# LEDs.net
KiCad netlist of a schematic drawn in Altium Designer
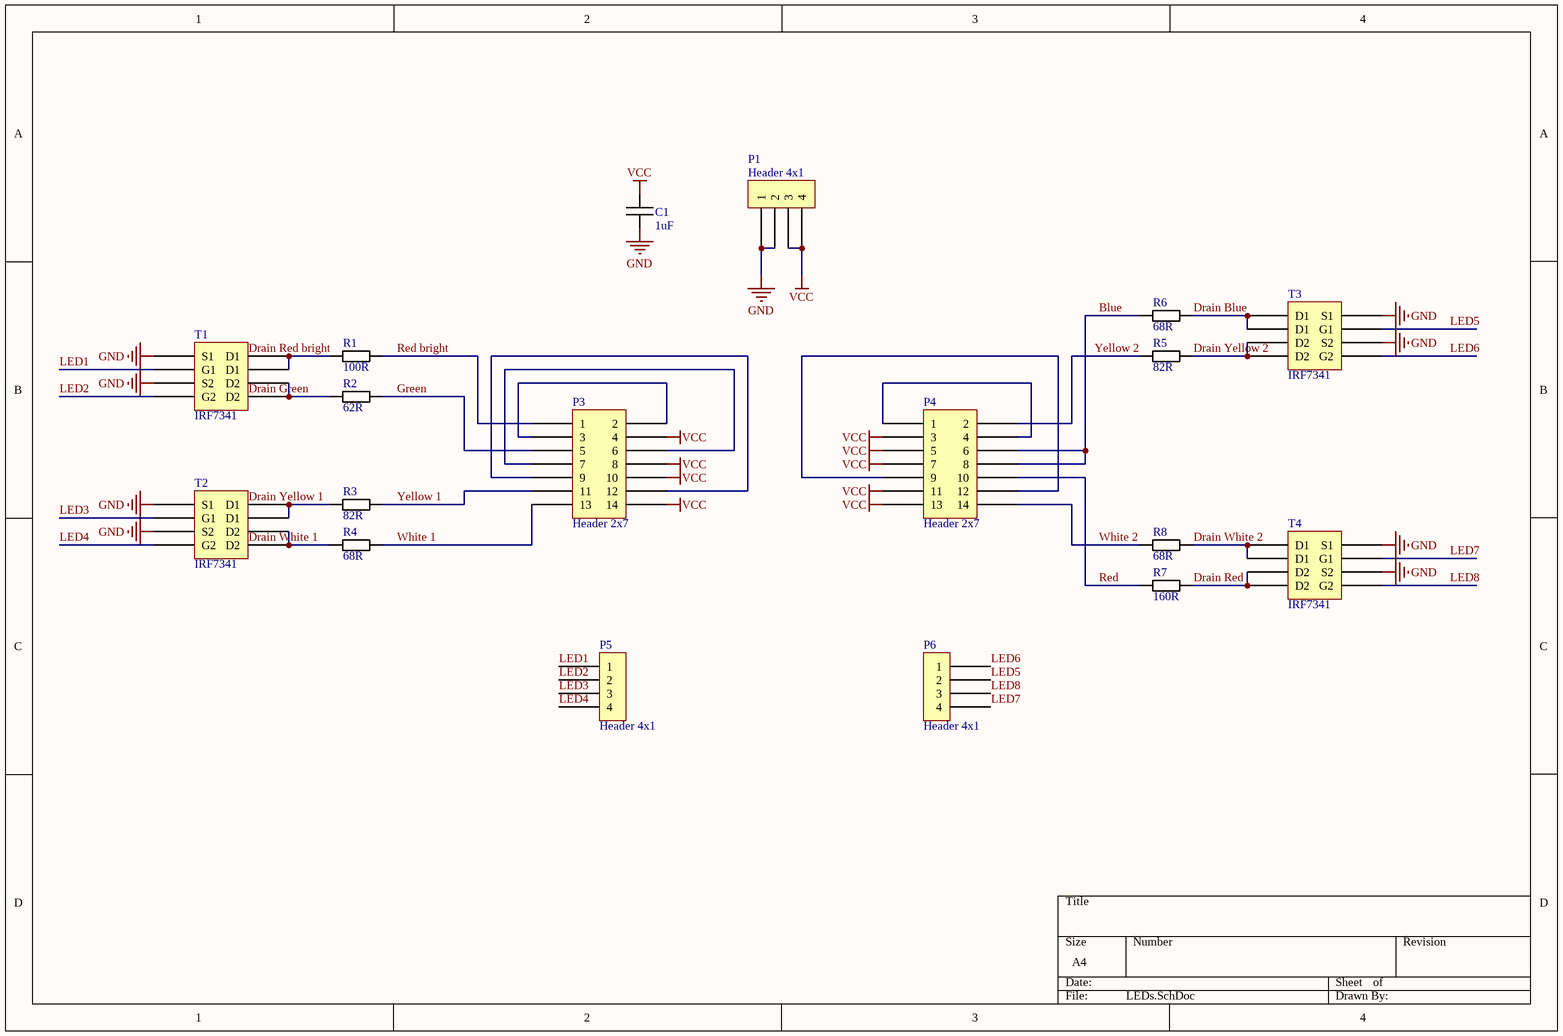
[diagram p0: LEDs.SchDoc]

(export (version "E")
  (design (tool "Eeschema 10.0.6"))
  (components
    (comp (ref "C1") (value "1uF") (footprint "C 0805 / 2012") (libsource (lib "LEDs") (part "Capacitor")))
    (comp (ref "P1")
      (value "Header 4x1")
      (footprint "Header 4x1 2.54mm")
      (libsource (lib "") (part "Header 4x1_1"))
    )
    (comp (ref "P3")
      (value "Header 2x7")
      (footprint "Header 7x2 2.54mm")
      (libsource (lib "LEDs") (part "Header 2x7"))
    )
    (comp (ref "P4")
      (value "Header 2x7")
      (footprint "Header 7x2 2.54mm")
      (libsource (lib "LEDs") (part "Header 2x7"))
    )
    (comp (ref "P5")
      (value "Header 4x1")
      (footprint "Header 4x1 2.54mm")
      (libsource (lib "") (part "Header 4x1_2"))
    )
    (comp (ref "P6")
      (value "Header 4x1")
      (footprint "Header 4x1 2.54mm")
      (libsource (lib "LEDs") (part "Header 4x1"))
    )
    (comp (ref "R1")
      (value "100R")
      (footprint "R 0805 / 2012")
      (description "Resistor")
      (libsource (lib "LEDs") (part "Resistor"))
    )
    (comp (ref "R2")
      (value "62R")
      (footprint "R 0805 / 2012")
      (description "Resistor")
      (libsource (lib "LEDs") (part "Resistor"))
    )
    (comp (ref "R3")
      (value "82R")
      (footprint "R 0805 / 2012")
      (description "Resistor")
      (libsource (lib "LEDs") (part "Resistor"))
    )
    (comp (ref "R4")
      (value "68R")
      (footprint "R 0805 / 2012")
      (description "Resistor")
      (libsource (lib "LEDs") (part "Resistor"))
    )
    (comp (ref "R5")
      (value "82R")
      (footprint "R 0805 / 2012")
      (description "Resistor")
      (libsource (lib "LEDs") (part "Resistor"))
    )
    (comp (ref "R6")
      (value "68R")
      (footprint "R 0805 / 2012")
      (description "Resistor")
      (libsource (lib "LEDs") (part "Resistor"))
    )
    (comp (ref "R7")
      (value "160R")
      (footprint "R 0805 / 2012")
      (description "Resistor")
      (libsource (lib "LEDs") (part "Resistor"))
    )
    (comp (ref "R8")
      (value "68R")
      (footprint "R 0805 / 2012")
      (description "Resistor")
      (libsource (lib "LEDs") (part "Resistor"))
    )
    (comp (ref "T1") (value "IRF7341") (footprint "SOIC8") (libsource (lib "") (part "IRF7341_1")))
    (comp (ref "T2") (value "IRF7341") (footprint "SOIC8") (libsource (lib "") (part "IRF7341_1")))
    (comp (ref "T3") (value "IRF7341") (footprint "SOIC8") (libsource (lib "LEDs") (part "IRF7341")))
    (comp (ref "T4") (value "IRF7341") (footprint "SOIC8") (libsource (lib "LEDs") (part "IRF7341")))
  )
  (nets
    (net (code "1") (name "/Blue") (class "Default")
      (node (ref "P4") (pin "6") (pinfunction "6_6") (pintype "passive"))
      (node (ref "P4") (pin "8") (pinfunction "8_8") (pintype "passive"))
      (node (ref "R6") (pin "1") (pinfunction "1_1") (pintype "passive"))
    )
    (net (code "2") (name "/Drain Blue") (class "Default")
      (node (ref "R6") (pin "2") (pinfunction "2_2") (pintype "passive"))
      (node (ref "T3") (pin "7") (pinfunction "D1_7") (pintype "passive"))
      (node (ref "T3") (pin "8") (pinfunction "D1_8") (pintype "passive"))
    )
    (net (code "4") (name "/Drain Red") (class "Default")
      (node (ref "R7") (pin "2") (pinfunction "2_2") (pintype "passive"))
      (node (ref "T4") (pin "5") (pinfunction "D2_5") (pintype "passive"))
      (node (ref "T4") (pin "6") (pinfunction "D2_6") (pintype "passive"))
    )
    (net (code "7") (name "/Drain White 2") (class "Default")
      (node (ref "R8") (pin "2") (pinfunction "2_2") (pintype "passive"))
      (node (ref "T4") (pin "7") (pinfunction "D1_7") (pintype "passive"))
      (node (ref "T4") (pin "8") (pinfunction "D1_8") (pintype "passive"))
    )
    (net (code "9") (name "/Drain Yellow 2") (class "Default")
      (node (ref "R5") (pin "2") (pinfunction "2_2") (pintype "passive"))
      (node (ref "T3") (pin "5") (pinfunction "D2_5") (pintype "passive"))
      (node (ref "T3") (pin "6") (pinfunction "D2_6") (pintype "passive"))
    )
    (net (code "10") (name "/Green") (class "Default")
      (node (ref "P3") (pin "5") (pinfunction "5_5") (pintype "passive"))
      (node (ref "R2") (pin "2") (pinfunction "2_2") (pintype "passive"))
    )
    (net (code "11") (name "/LED1") (class "Default")
      (node (ref "P5") (pin "1") (pinfunction "1_1") (pintype "passive"))
      (node (ref "T1") (pin "2") (pinfunction "G1_2") (pintype "passive"))
    )
    (net (code "12") (name "/LED2") (class "Default")
      (node (ref "P5") (pin "2") (pinfunction "2_2") (pintype "passive"))
      (node (ref "T1") (pin "4") (pinfunction "G2_4") (pintype "passive"))
    )
    (net (code "13") (name "/LED3") (class "Default")
      (node (ref "P5") (pin "3") (pinfunction "3_3") (pintype "passive"))
      (node (ref "T2") (pin "2") (pinfunction "G1_2") (pintype "passive"))
    )
    (net (code "14") (name "/LED4") (class "Default")
      (node (ref "P5") (pin "4") (pinfunction "4_4") (pintype "passive"))
      (node (ref "T2") (pin "4") (pinfunction "G2_4") (pintype "passive"))
    )
    (net (code "15") (name "/LED5") (class "Default")
      (node (ref "P6") (pin "2") (pinfunction "2_2") (pintype "passive"))
      (node (ref "T3") (pin "2") (pinfunction "G1_2") (pintype "passive"))
    )
    (net (code "16") (name "/LED6") (class "Default")
      (node (ref "P6") (pin "1") (pinfunction "1_1") (pintype "passive"))
      (node (ref "T3") (pin "4") (pinfunction "G2_4") (pintype "passive"))
    )
    (net (code "17") (name "/LED7") (class "Default")
      (node (ref "P6") (pin "4") (pinfunction "4_4") (pintype "passive"))
      (node (ref "T4") (pin "2") (pinfunction "G1_2") (pintype "passive"))
    )
    (net (code "18") (name "/LED8") (class "Default")
      (node (ref "P6") (pin "3") (pinfunction "3_3") (pintype "passive"))
      (node (ref "T4") (pin "4") (pinfunction "G2_4") (pintype "passive"))
    )
    (net (code "19") (name "/Red") (class "Default")
      (node (ref "P4") (pin "10") (pinfunction "10_10") (pintype "passive"))
      (node (ref "R7") (pin "1") (pinfunction "1_1") (pintype "passive"))
    )
    (net (code "20") (name "/Red bright") (class "Default")
      (node (ref "P3") (pin "1") (pinfunction "1_1") (pintype "passive"))
      (node (ref "R1") (pin "2") (pinfunction "2_2") (pintype "passive"))
    )
    (net (code "21") (name "/White 1") (class "Default")
      (node (ref "P3") (pin "13") (pinfunction "13_13") (pintype "passive"))
      (node (ref "R4") (pin "2") (pinfunction "2_2") (pintype "passive"))
    )
    (net (code "22") (name "/White 2") (class "Default")
      (node (ref "P4") (pin "14") (pinfunction "14_14") (pintype "passive"))
      (node (ref "R8") (pin "1") (pinfunction "1_1") (pintype "passive"))
    )
    (net (code "23") (name "/Yellow 1") (class "Default")
      (node (ref "P3") (pin "11") (pinfunction "11_11") (pintype "passive"))
      (node (ref "R3") (pin "2") (pinfunction "2_2") (pintype "passive"))
    )
    (net (code "24") (name "/Yellow 2") (class "Default")
      (node (ref "P4") (pin "2") (pinfunction "2_2") (pintype "passive"))
      (node (ref "R5") (pin "1") (pinfunction "1_1") (pintype "passive"))
    )
    (net (code "25") (name "GND") (class "Default")
      (node (ref "C1") (pin "2") (pinfunction "1_2") (pintype "passive"))
      (node (ref "P1") (pin "1") (pinfunction "1_1") (pintype "passive"))
      (node (ref "P1") (pin "2") (pinfunction "2_2") (pintype "passive"))
      (node (ref "T1") (pin "1") (pinfunction "S1_1") (pintype "passive"))
      (node (ref "T1") (pin "3") (pinfunction "S2_3") (pintype "passive"))
      (node (ref "T2") (pin "1") (pinfunction "S1_1") (pintype "passive"))
      (node (ref "T2") (pin "3") (pinfunction "S2_3") (pintype "passive"))
      (node (ref "T3") (pin "1") (pinfunction "S1_1") (pintype "passive"))
      (node (ref "T3") (pin "3") (pinfunction "S2_3") (pintype "passive"))
      (node (ref "T4") (pin "1") (pinfunction "S1_1") (pintype "passive"))
      (node (ref "T4") (pin "3") (pinfunction "S2_3") (pintype "passive"))
    )
    (net (code "26") (name "Net-(P3-Pad2)") (class "Default")
      (node (ref "P3") (pin "2") (pinfunction "2_2") (pintype "passive"))
      (node (ref "P3") (pin "3") (pinfunction "3_3") (pintype "passive"))
    )
    (net (code "27") (name "Net-(P3-Pad6)") (class "Default")
      (node (ref "P3") (pin "6") (pinfunction "6_6") (pintype "passive"))
      (node (ref "P3") (pin "7") (pinfunction "7_7") (pintype "passive"))
    )
    (net (code "28") (name "Net-(P3-Pad12)") (class "Default")
      (node (ref "P3") (pin "12") (pinfunction "12_12") (pintype "passive"))
      (node (ref "P3") (pin "9") (pinfunction "9_9") (pintype "passive"))
    )
    (net (code "29") (name "Net-(P4-Pad1)") (class "Default")
      (node (ref "P4") (pin "1") (pinfunction "1_1") (pintype "passive"))
      (node (ref "P4") (pin "4") (pinfunction "4_4") (pintype "passive"))
    )
    (net (code "30") (name "Net-(P4-Pad12)") (class "Default")
      (node (ref "P4") (pin "12") (pinfunction "12_12") (pintype "passive"))
      (node (ref "P4") (pin "9") (pinfunction "9_9") (pintype "passive"))
    )
    (net (code "31") (name "Net-(R1-Pad1)") (class "Default")
      (node (ref "R1") (pin "1") (pinfunction "1_1") (pintype "passive"))
      (node (ref "T1") (pin "7") (pinfunction "D1_7") (pintype "passive"))
      (node (ref "T1") (pin "8") (pinfunction "D1_8") (pintype "passive"))
    )
    (net (code "32") (name "Net-(R2-Pad1)") (class "Default")
      (node (ref "R2") (pin "1") (pinfunction "1_1") (pintype "passive"))
      (node (ref "T1") (pin "5") (pinfunction "D2_5") (pintype "passive"))
      (node (ref "T1") (pin "6") (pinfunction "D2_6") (pintype "passive"))
    )
    (net (code "33") (name "Net-(R3-Pad1)") (class "Default")
      (node (ref "R3") (pin "1") (pinfunction "1_1") (pintype "passive"))
      (node (ref "T2") (pin "7") (pinfunction "D1_7") (pintype "passive"))
      (node (ref "T2") (pin "8") (pinfunction "D1_8") (pintype "passive"))
    )
    (net (code "34") (name "Net-(R4-Pad1)") (class "Default")
      (node (ref "R4") (pin "1") (pinfunction "1_1") (pintype "passive"))
      (node (ref "T2") (pin "5") (pinfunction "D2_5") (pintype "passive"))
      (node (ref "T2") (pin "6") (pinfunction "D2_6") (pintype "passive"))
    )
    (net (code "35") (name "VCC") (class "Default")
      (node (ref "C1") (pin "1") (pinfunction "1_1") (pintype "passive"))
      (node (ref "P1") (pin "3") (pinfunction "3_3") (pintype "passive"))
      (node (ref "P1") (pin "4") (pinfunction "4_4") (pintype "passive"))
      (node (ref "P3") (pin "10") (pinfunction "10_10") (pintype "passive"))
      (node (ref "P3") (pin "14") (pinfunction "14_14") (pintype "passive"))
      (node (ref "P3") (pin "4") (pinfunction "4_4") (pintype "passive"))
      (node (ref "P3") (pin "8") (pinfunction "8_8") (pintype "passive"))
      (node (ref "P4") (pin "11") (pinfunction "11_11") (pintype "passive"))
      (node (ref "P4") (pin "13") (pinfunction "13_13") (pintype "passive"))
      (node (ref "P4") (pin "3") (pinfunction "3_3") (pintype "passive"))
      (node (ref "P4") (pin "5") (pinfunction "5_5") (pintype "passive"))
      (node (ref "P4") (pin "7") (pinfunction "7_7") (pintype "passive"))
    )
  )
)
